# balvin.net
KiCad netlist of a schematic drawn in EAGLE
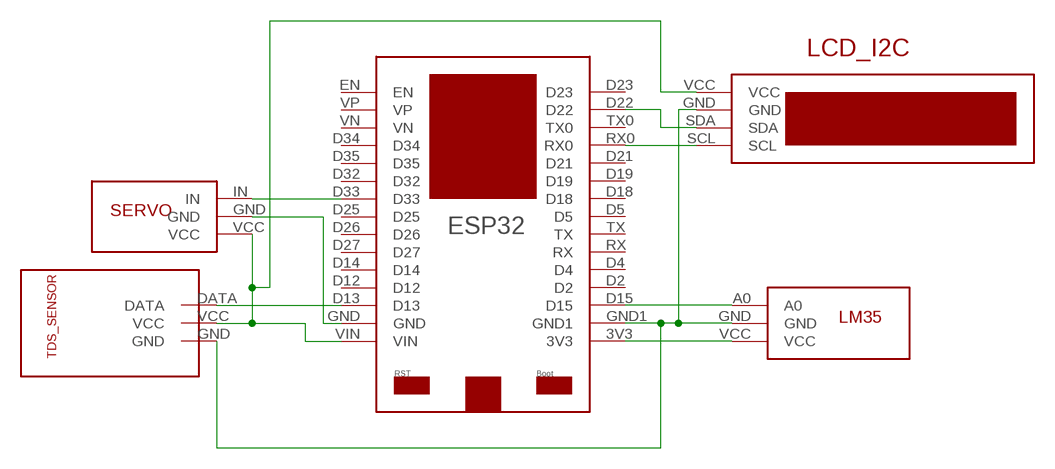
[diagram p0: schematic, sheet 1]

(export (version "E")
  (design (tool "Eeschema 10.0.6"))
  (components
    (comp (ref "U$1")
      (value "ESP32")
      (footprint "eagle-import:ESP32")
      (libsource (lib "eagle-import") (part "ESP32"))
    )
    (comp (ref "U$2")
      (value "TDS_SENSOR")
      (footprint "eagle-import:TDS_SENSOR")
      (libsource (lib "eagle-import") (part "TDS_SENSOR"))
    )
    (comp (ref "U$3")
      (value "LM35_SENSOR")
      (footprint "eagle-import:LM35_SENSOR")
      (libsource (lib "eagle-import") (part "LM35_SENSOR"))
    )
    (comp (ref "U$4")
      (value "SERVO_MOTOR")
      (footprint "eagle-import:SERVO_MOTOR")
      (libsource (lib "eagle-import") (part "SERVO_MOTOR"))
    )
    (comp (ref "U$5")
      (value "LCD_I2C")
      (footprint "eagle-import:LCD_I2C")
      (libsource (lib "eagle-import") (part "LCD_I2C"))
    )
  )
  (nets
    (net (code "1") (name "Net-(U$1-Pad3V3)") (class "Default")
      (node (ref "U$1") (pin "3V3") (pinfunction "3V3_3V3") (pintype "bidirectional"))
      (node (ref "U$3") (pin "VCC") (pinfunction "VCC_VCC") (pintype "bidirectional"))
    )
    (net (code "2") (name "Net-(U$1-PadD13)") (class "Default")
      (node (ref "U$1") (pin "D13") (pinfunction "D13_D13") (pintype "bidirectional"))
      (node (ref "U$2") (pin "DATA") (pinfunction "DATA_DATA") (pintype "bidirectional"))
    )
    (net (code "3") (name "Net-(U$1-PadD15)") (class "Default")
      (node (ref "U$1") (pin "D15") (pinfunction "D15_D15") (pintype "bidirectional"))
      (node (ref "U$3") (pin "A0") (pinfunction "A0_A0") (pintype "bidirectional"))
    )
    (net (code "4") (name "Net-(U$1-PadD22)") (class "Default")
      (node (ref "U$1") (pin "D22") (pinfunction "D22_D22") (pintype "bidirectional"))
      (node (ref "U$5") (pin "SDA") (pinfunction "SDA_SDA") (pintype "bidirectional"))
    )
    (net (code "5") (name "Net-(U$1-PadD33)") (class "Default")
      (node (ref "U$1") (pin "D33") (pinfunction "D33_D33") (pintype "bidirectional"))
      (node (ref "U$4") (pin "IN") (pinfunction "IN_IN") (pintype "bidirectional"))
    )
    (net (code "6") (name "Net-(U$1-PadGND)") (class "Default")
      (node (ref "U$1") (pin "GND") (pinfunction "GND_GND") (pintype "bidirectional"))
      (node (ref "U$4") (pin "GND") (pinfunction "GND_GND") (pintype "bidirectional"))
    )
    (net (code "7") (name "Net-(U$1-PadGND1)") (class "Default")
      (node (ref "U$1") (pin "GND1") (pinfunction "GND1_GND1") (pintype "bidirectional"))
      (node (ref "U$2") (pin "GND") (pinfunction "GND_GND") (pintype "bidirectional"))
      (node (ref "U$3") (pin "GND") (pinfunction "GND_GND") (pintype "bidirectional"))
      (node (ref "U$5") (pin "GND") (pinfunction "GND_GND") (pintype "bidirectional"))
    )
    (net (code "8") (name "Net-(U$1-PadRX0)") (class "Default")
      (node (ref "U$1") (pin "RX0") (pinfunction "RX0_RX0") (pintype "bidirectional"))
      (node (ref "U$5") (pin "SCL") (pinfunction "SCL_SCL") (pintype "bidirectional"))
    )
    (net (code "9") (name "Net-(U$1-PadVIN)") (class "Default")
      (node (ref "U$1") (pin "VIN") (pinfunction "VIN_VIN") (pintype "bidirectional"))
      (node (ref "U$2") (pin "VCC") (pinfunction "VCC_VCC") (pintype "bidirectional"))
      (node (ref "U$4") (pin "VCC") (pinfunction "VCC_VCC") (pintype "bidirectional"))
      (node (ref "U$5") (pin "VCC") (pinfunction "VCC_VCC") (pintype "bidirectional"))
    )
    (net (code "10") (name "unconnected-(U$1-PadD2)") (class "Default")
      (node (ref "U$1") (pin "D2") (pinfunction "D2_D2") (pintype "bidirectional"))
    )
    (net (code "11") (name "unconnected-(U$1-PadD4)") (class "Default")
      (node (ref "U$1") (pin "D4") (pinfunction "D4_D4") (pintype "bidirectional"))
    )
    (net (code "12") (name "unconnected-(U$1-PadD5)") (class "Default")
      (node (ref "U$1") (pin "D5") (pinfunction "D5_D5") (pintype "bidirectional"))
    )
    (net (code "13") (name "unconnected-(U$1-PadD12)") (class "Default")
      (node (ref "U$1") (pin "D12") (pinfunction "D12_D12") (pintype "bidirectional"))
    )
    (net (code "14") (name "unconnected-(U$1-PadD14)") (class "Default")
      (node (ref "U$1") (pin "D14") (pinfunction "D14_D14") (pintype "bidirectional"))
    )
    (net (code "15") (name "unconnected-(U$1-PadD18)") (class "Default")
      (node (ref "U$1") (pin "D18") (pinfunction "D18_D18") (pintype "bidirectional"))
    )
    (net (code "16") (name "unconnected-(U$1-PadD19)") (class "Default")
      (node (ref "U$1") (pin "D19") (pinfunction "D19_D19") (pintype "bidirectional"))
    )
    (net (code "17") (name "unconnected-(U$1-PadD21)") (class "Default")
      (node (ref "U$1") (pin "D21") (pinfunction "D21_D21") (pintype "bidirectional"))
    )
    (net (code "18") (name "unconnected-(U$1-PadD23)") (class "Default")
      (node (ref "U$1") (pin "D23") (pinfunction "D23_D23") (pintype "bidirectional"))
    )
    (net (code "19") (name "unconnected-(U$1-PadD25)") (class "Default")
      (node (ref "U$1") (pin "D25") (pinfunction "D25_D25") (pintype "bidirectional"))
    )
    (net (code "20") (name "unconnected-(U$1-PadD26)") (class "Default")
      (node (ref "U$1") (pin "D26") (pinfunction "D26_D26") (pintype "bidirectional"))
    )
    (net (code "21") (name "unconnected-(U$1-PadD27)") (class "Default")
      (node (ref "U$1") (pin "D27") (pinfunction "D27_D27") (pintype "bidirectional"))
    )
    (net (code "22") (name "unconnected-(U$1-PadD32)") (class "Default")
      (node (ref "U$1") (pin "D32") (pinfunction "D32_D32") (pintype "bidirectional"))
    )
    (net (code "23") (name "unconnected-(U$1-PadD34)") (class "Default")
      (node (ref "U$1") (pin "D34") (pinfunction "D34_D34") (pintype "bidirectional"))
    )
    (net (code "24") (name "unconnected-(U$1-PadD35)") (class "Default")
      (node (ref "U$1") (pin "D35") (pinfunction "D35_D35") (pintype "bidirectional"))
    )
    (net (code "25") (name "unconnected-(U$1-PadEN)") (class "Default")
      (node (ref "U$1") (pin "EN") (pinfunction "EN_EN") (pintype "bidirectional"))
    )
    (net (code "26") (name "unconnected-(U$1-PadRX)") (class "Default")
      (node (ref "U$1") (pin "RX") (pinfunction "RX_RX") (pintype "bidirectional"))
    )
    (net (code "27") (name "unconnected-(U$1-PadTX)") (class "Default")
      (node (ref "U$1") (pin "TX") (pinfunction "TX_TX") (pintype "bidirectional"))
    )
    (net (code "28") (name "unconnected-(U$1-PadTX0)") (class "Default")
      (node (ref "U$1") (pin "TX0") (pinfunction "TX0_TX0") (pintype "bidirectional"))
    )
    (net (code "29") (name "unconnected-(U$1-PadVN)") (class "Default")
      (node (ref "U$1") (pin "VN") (pinfunction "VN_VN") (pintype "bidirectional"))
    )
    (net (code "30") (name "unconnected-(U$1-PadVP)") (class "Default")
      (node (ref "U$1") (pin "VP") (pinfunction "VP_VP") (pintype "bidirectional"))
    )
  )
)
